# LaserExposer.net
KiCad netlist of a schematic drawn in EAGLE
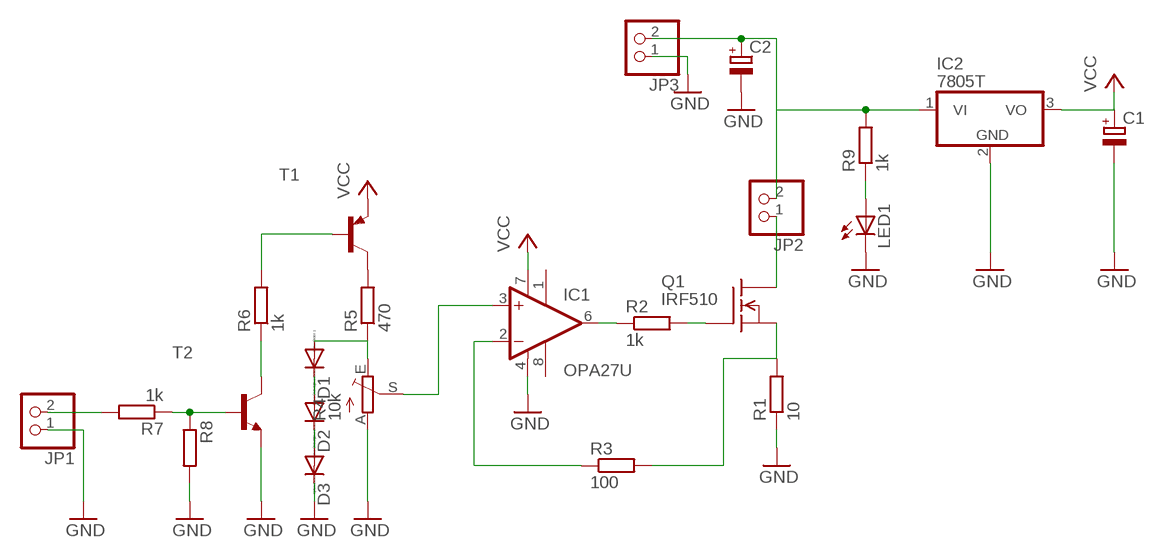
[diagram p0: schematic, sheet 1]

(export (version "E")
  (design (tool "Eeschema 10.0.6"))
  (components
    (comp (ref "C1")
      (value "CPOL-EUE5-10.5")
      (footprint "eagle-import:E5-10,5")
      (libsource (lib "eagle-import") (part "CPOL-EUE5-10.5"))
    )
    (comp (ref "C2")
      (value "CPOL-EUE5-10.5")
      (footprint "eagle-import:E5-10,5")
      (libsource (lib "eagle-import") (part "CPOL-EUE5-10.5"))
    )
    (comp (ref "D1")
      (value "DIODE-DO214AA")
      (footprint "eagle-import:DO214AA")
      (libsource (lib "eagle-import") (part "DIODE-DO214AA"))
    )
    (comp (ref "D2")
      (value "DIODE-DO214AA")
      (footprint "eagle-import:DO214AA")
      (libsource (lib "eagle-import") (part "DIODE-DO214AA"))
    )
    (comp (ref "D3")
      (value "DIODE-DO214AA")
      (footprint "eagle-import:DO214AA")
      (libsource (lib "eagle-import") (part "DIODE-DO214AA"))
    )
    (comp (ref "IC1")
      (value "OPA27U")
      (footprint "eagle-import:SO08")
      (libsource (lib "eagle-import") (part "OPA?U27"))
    )
    (comp (ref "IC2")
      (value "7805T")
      (footprint "eagle-import:TO220H")
      (libsource (lib "eagle-import") (part "78T05"))
    )
    (comp (ref "JP1")
      (value "PINHD-1X2")
      (footprint "eagle-import:1X02")
      (libsource (lib "eagle-import") (part "PINHD-1X2"))
    )
    (comp (ref "JP2")
      (value "PINHD-1X2")
      (footprint "eagle-import:1X02")
      (libsource (lib "eagle-import") (part "PINHD-1X2"))
    )
    (comp (ref "JP3")
      (value "PINHD-1X2")
      (footprint "eagle-import:1X02")
      (libsource (lib "eagle-import") (part "PINHD-1X2"))
    )
    (comp (ref "LED1")
      (value "LEDCHIP-LED0805")
      (footprint "eagle-import:CHIP-LED0805")
      (libsource (lib "eagle-import") (part "LEDCHIP-LED0805"))
    )
    (comp (ref "Q1")
      (value "IRF510")
      (footprint "eagle-import:TO220")
      (libsource (lib "eagle-import") (part "IRF510"))
    )
    (comp (ref "R1")
      (value "10")
      (footprint "eagle-import:0207_10")
      (libsource (lib "eagle-import") (part "R-EU_0207/10"))
    )
    (comp (ref "R2")
      (value "1k")
      (footprint "eagle-import:R1206")
      (libsource (lib "eagle-import") (part "R-EU_R1206"))
    )
    (comp (ref "R3")
      (value "100")
      (footprint "eagle-import:R1206")
      (libsource (lib "eagle-import") (part "R-EU_R1206"))
    )
    (comp (ref "R4")
      (value "10k")
      (footprint "eagle-import:SP19L")
      (libsource (lib "eagle-import") (part "TRIM_EU-B90P"))
    )
    (comp (ref "R5")
      (value "470")
      (footprint "eagle-import:R1206")
      (libsource (lib "eagle-import") (part "R-EU_R1206"))
    )
    (comp (ref "R6")
      (value "1k")
      (footprint "eagle-import:R1206")
      (libsource (lib "eagle-import") (part "R-EU_R1206"))
    )
    (comp (ref "R7")
      (value "1k")
      (footprint "eagle-import:R1206")
      (libsource (lib "eagle-import") (part "R-EU_R1206"))
    )
    (comp (ref "R8")
      (value "R-EU_R1206")
      (footprint "eagle-import:R1206")
      (libsource (lib "eagle-import") (part "R-EU_R1206"))
    )
    (comp (ref "R9")
      (value "1k")
      (footprint "eagle-import:R1206")
      (libsource (lib "eagle-import") (part "R-EU_R1206"))
    )
    (comp (ref "T1")
      (value "MMBT3906LT1-PNP-SOT23-BEC")
      (footprint "eagle-import:SOT23-BEC")
      (libsource (lib "eagle-import") (part "-PNP-SOT23-BECMMBT3906LT1"))
    )
    (comp (ref "T2")
      (value "BC817-16-NPN-SOT23-BEC")
      (footprint "eagle-import:SOT23-BEC")
      (libsource (lib "eagle-import") (part "-NPN-SOT23-BECBC817-16"))
    )
  )
  (nets
    (net (code "1") (name "GND") (class "Default")
      (node (ref "C1") (pin "-") (pinfunction "-_-") (pintype "passive"))
      (node (ref "C2") (pin "-") (pinfunction "-_-") (pintype "passive"))
      (node (ref "D3") (pin "C") (pinfunction "C_C") (pintype "passive"))
      (node (ref "IC1") (pin "4") (pinfunction "V-_4") (pintype "power_in"))
      (node (ref "IC2") (pin "2") (pinfunction "GND_2") (pintype "passive"))
      (node (ref "JP1") (pin "1") (pinfunction "1_1") (pintype "passive"))
      (node (ref "JP3") (pin "1") (pinfunction "1_1") (pintype "passive"))
      (node (ref "LED1") (pin "C") (pinfunction "C_C") (pintype "passive"))
      (node (ref "R1") (pin "1") (pinfunction "1_1") (pintype "passive"))
      (node (ref "R4") (pin "A") (pinfunction "A_A") (pintype "passive"))
      (node (ref "R8") (pin "2") (pinfunction "2_2") (pintype "passive"))
      (node (ref "T2") (pin "E") (pinfunction "E_E") (pintype "passive"))
    )
    (net (code "2") (name "Net-(D1-PadA)") (class "Default")
      (node (ref "D1") (pin "A") (pinfunction "A_A") (pintype "passive"))
      (node (ref "R4") (pin "E") (pinfunction "E_E") (pintype "passive"))
      (node (ref "R5") (pin "1") (pinfunction "1_1") (pintype "passive"))
    )
    (net (code "3") (name "Net-(D1-PadC)") (class "Default")
      (node (ref "D1") (pin "C") (pinfunction "C_C") (pintype "passive"))
      (node (ref "D2") (pin "A") (pinfunction "A_A") (pintype "passive"))
    )
    (net (code "4") (name "Net-(D2-PadC)") (class "Default")
      (node (ref "D2") (pin "C") (pinfunction "C_C") (pintype "passive"))
      (node (ref "D3") (pin "A") (pinfunction "A_A") (pintype "passive"))
    )
    (net (code "5") (name "Net-(IC1-+IN)") (class "Default")
      (node (ref "IC1") (pin "3") (pinfunction "+IN_3") (pintype "input"))
      (node (ref "R4") (pin "S") (pinfunction "S_S") (pintype "passive"))
    )
    (net (code "6") (name "Net-(IC1--IN)") (class "Default")
      (node (ref "IC1") (pin "2") (pinfunction "-IN_2") (pintype "input"))
      (node (ref "R3") (pin "1") (pinfunction "1_1") (pintype "passive"))
    )
    (net (code "7") (name "Net-(IC1-OUT)") (class "Default")
      (node (ref "IC1") (pin "6") (pinfunction "OUT_6") (pintype "output"))
      (node (ref "R2") (pin "1") (pinfunction "1_1") (pintype "passive"))
    )
    (net (code "8") (name "Net-(IC2-VI)") (class "Default")
      (node (ref "C2") (pin "+") (pinfunction "+_+") (pintype "passive"))
      (node (ref "IC2") (pin "1") (pinfunction "VI_1") (pintype "input"))
      (node (ref "JP2") (pin "2") (pinfunction "2_2") (pintype "passive"))
      (node (ref "JP3") (pin "2") (pinfunction "2_2") (pintype "passive"))
      (node (ref "R9") (pin "2") (pinfunction "2_2") (pintype "passive"))
    )
    (net (code "9") (name "Net-(JP1-Pad2)") (class "Default")
      (node (ref "JP1") (pin "2") (pinfunction "2_2") (pintype "passive"))
      (node (ref "R7") (pin "2") (pinfunction "2_2") (pintype "passive"))
    )
    (net (code "10") (name "Net-(LED1-PadA)") (class "Default")
      (node (ref "LED1") (pin "A") (pinfunction "A_A") (pintype "passive"))
      (node (ref "R9") (pin "1") (pinfunction "1_1") (pintype "passive"))
    )
    (net (code "11") (name "Net-(Q1-D)") (class "Default")
      (node (ref "JP2") (pin "1") (pinfunction "1_1") (pintype "passive"))
      (node (ref "Q1") (pin "2") (pinfunction "D_2") (pintype "passive"))
    )
    (net (code "12") (name "Net-(Q1-G)") (class "Default")
      (node (ref "Q1") (pin "1") (pinfunction "G_1") (pintype "passive"))
      (node (ref "R2") (pin "2") (pinfunction "2_2") (pintype "passive"))
    )
    (net (code "13") (name "Net-(Q1-S)") (class "Default")
      (node (ref "Q1") (pin "3") (pinfunction "S_3") (pintype "passive"))
      (node (ref "R1") (pin "2") (pinfunction "2_2") (pintype "passive"))
      (node (ref "R3") (pin "2") (pinfunction "2_2") (pintype "passive"))
    )
    (net (code "14") (name "Net-(R5-Pad2)") (class "Default")
      (node (ref "R5") (pin "2") (pinfunction "2_2") (pintype "passive"))
      (node (ref "T1") (pin "C") (pinfunction "C_C") (pintype "passive"))
    )
    (net (code "15") (name "Net-(R6-Pad1)") (class "Default")
      (node (ref "R6") (pin "1") (pinfunction "1_1") (pintype "passive"))
      (node (ref "T2") (pin "C") (pinfunction "C_C") (pintype "passive"))
    )
    (net (code "16") (name "Net-(R6-Pad2)") (class "Default")
      (node (ref "R6") (pin "2") (pinfunction "2_2") (pintype "passive"))
      (node (ref "T1") (pin "B") (pinfunction "B_B") (pintype "passive"))
    )
    (net (code "17") (name "Net-(R7-Pad1)") (class "Default")
      (node (ref "R7") (pin "1") (pinfunction "1_1") (pintype "passive"))
      (node (ref "R8") (pin "1") (pinfunction "1_1") (pintype "passive"))
      (node (ref "T2") (pin "B") (pinfunction "B_B") (pintype "passive"))
    )
    (net (code "18") (name "VCC") (class "Default")
      (node (ref "C1") (pin "+") (pinfunction "+_+") (pintype "passive"))
      (node (ref "IC1") (pin "7") (pinfunction "V+_7") (pintype "power_in"))
      (node (ref "IC2") (pin "3") (pinfunction "VO_3") (pintype "passive"))
      (node (ref "T1") (pin "E") (pinfunction "E_E") (pintype "passive"))
    )
    (net (code "19") (name "unconnected-(IC1-OFF1-Pad1)") (class "Default")
      (node (ref "IC1") (pin "1") (pinfunction "OFF1_1") (pintype "passive"))
    )
    (net (code "20") (name "unconnected-(IC1-OFF2-Pad8)") (class "Default")
      (node (ref "IC1") (pin "8") (pinfunction "OFF2_8") (pintype "passive"))
    )
  )
)
